# multivideo.net
KiCad netlist of a schematic drawn in EAGLE
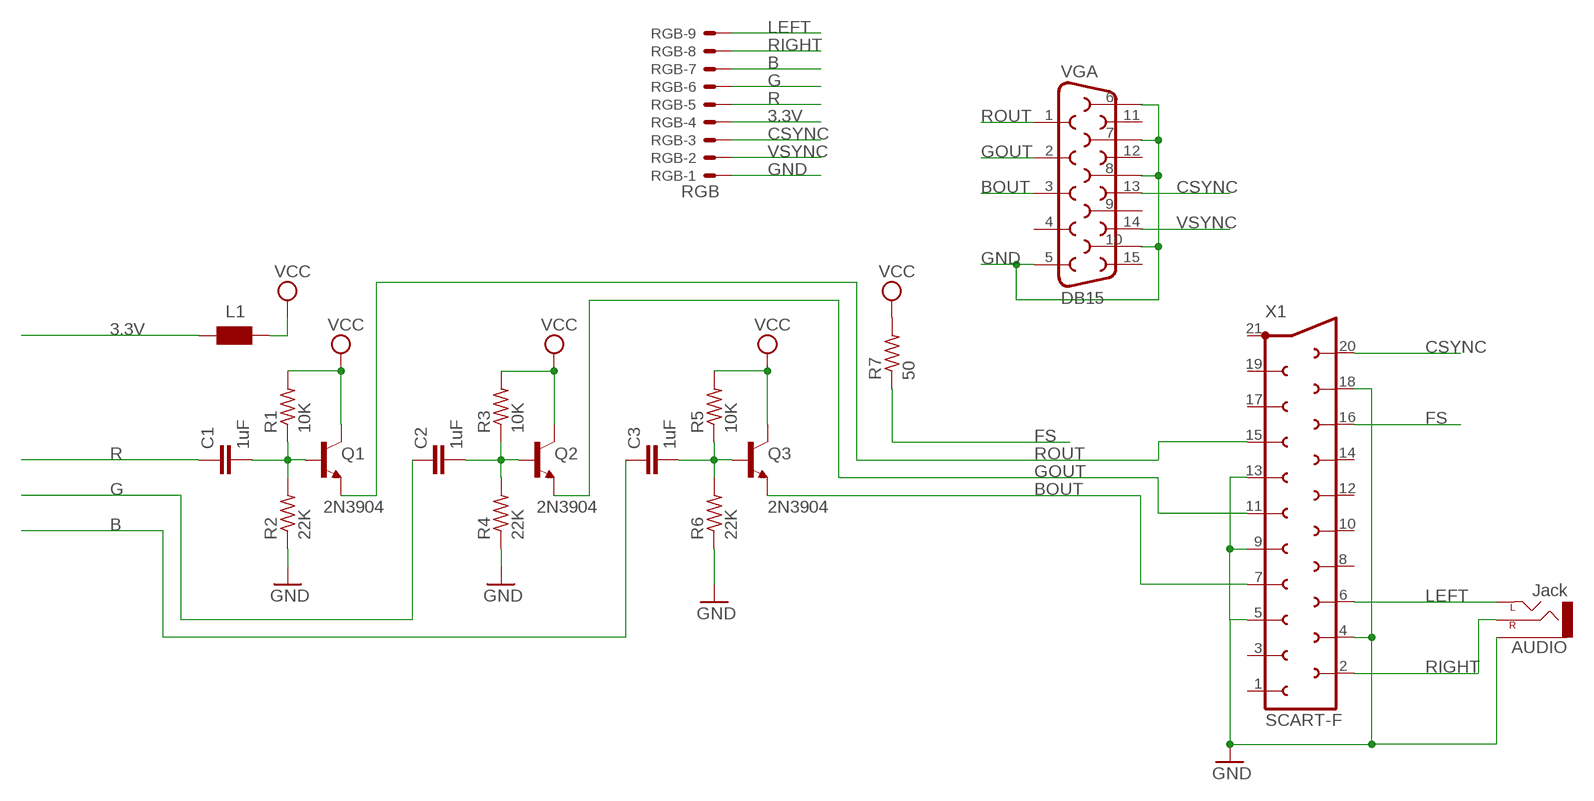
[diagram p0: schematic, sheet 1]

(export (version "E")
  (design (tool "Eeschema 10.0.6"))
  (components
    (comp (ref "AUDIO")
      (value "Jack")
      (footprint "eagle-import:AUDIO-JACK")
      (libsource (lib "eagle-import") (part "AUDIO-JACKPTH"))
    )
    (comp (ref "C1")
      (value "1uF")
      (footprint "eagle-import:C1206K")
      (libsource (lib "eagle-import") (part "C-EUC1206K"))
    )
    (comp (ref "C2")
      (value "1uF")
      (footprint "eagle-import:C1206K")
      (libsource (lib "eagle-import") (part "C-EUC1206K"))
    )
    (comp (ref "C3")
      (value "1uF")
      (footprint "eagle-import:C1206K")
      (libsource (lib "eagle-import") (part "C-EUC1206K"))
    )
    (comp (ref "L1")
      (value "WE-CBF_0805")
      (footprint "eagle-import:0805")
      (libsource (lib "eagle-import") (part "WE-CBF_0805"))
    )
    (comp (ref "Q1")
      (value "2N3904")
      (footprint "eagle-import:SOT23")
      (libsource (lib "eagle-import") (part "BC847SMDC"))
    )
    (comp (ref "Q2")
      (value "2N3904")
      (footprint "eagle-import:SOT23")
      (libsource (lib "eagle-import") (part "BC847SMDC"))
    )
    (comp (ref "Q3")
      (value "2N3904")
      (footprint "eagle-import:SOT23")
      (libsource (lib "eagle-import") (part "BC847SMDC"))
    )
    (comp (ref "R1")
      (value "10K")
      (footprint "eagle-import:R0805")
      (libsource (lib "eagle-import") (part "R-US_R0805"))
    )
    (comp (ref "R2")
      (value "22K")
      (footprint "eagle-import:R0805")
      (libsource (lib "eagle-import") (part "R-US_R0805"))
    )
    (comp (ref "R3")
      (value "10K")
      (footprint "eagle-import:R0805")
      (libsource (lib "eagle-import") (part "R-US_R0805"))
    )
    (comp (ref "R4")
      (value "22K")
      (footprint "eagle-import:R0805")
      (libsource (lib "eagle-import") (part "R-US_R0805"))
    )
    (comp (ref "R5")
      (value "10K")
      (footprint "eagle-import:R0805")
      (libsource (lib "eagle-import") (part "R-US_R0805"))
    )
    (comp (ref "R6")
      (value "22K")
      (footprint "eagle-import:R0805")
      (libsource (lib "eagle-import") (part "R-US_R0805"))
    )
    (comp (ref "R7")
      (value "50")
      (footprint "eagle-import:R0805")
      (libsource (lib "eagle-import") (part "R-US_R0805"))
    )
    (comp (ref "RGB")
      (value "RGB")
      (footprint "eagle-import:53048-09")
      (fields (field (name "MPN") "53048-0910"))
      (libsource (lib "eagle-import") (part "53?-09048"))
    )
    (comp (ref "VGA")
      (value "DB15")
      (footprint "eagle-import:DB15")
      (libsource (lib "eagle-import") (part "DB15"))
    )
    (comp (ref "X1")
      (value "SCART-F")
      (footprint "eagle-import:SCART-F")
      (libsource (lib "eagle-import") (part "SCART-F"))
    )
  )
  (nets
    (net (code "1") (name "/3.3V") (class "Default")
      (node (ref "L1") (pin "1") (pinfunction "1_1") (pintype "passive"))
      (node (ref "RGB") (pin "4") (pinfunction "S_4") (pintype "passive"))
    )
    (net (code "2") (name "/B") (class "Default")
      (node (ref "C3") (pin "1") (pinfunction "1_1") (pintype "passive"))
      (node (ref "RGB") (pin "7") (pinfunction "S_7") (pintype "passive"))
    )
    (net (code "3") (name "/BOUT") (class "Default")
      (node (ref "Q3") (pin "2") (pinfunction "E_2") (pintype "passive"))
      (node (ref "VGA") (pin "3") (pinfunction "3_3") (pintype "passive"))
      (node (ref "X1") (pin "7") (pinfunction "7_7") (pintype "passive"))
    )
    (net (code "4") (name "/CSYNC") (class "Default")
      (node (ref "RGB") (pin "3") (pinfunction "S_3") (pintype "passive"))
      (node (ref "VGA") (pin "13") (pinfunction "13_13") (pintype "passive"))
      (node (ref "X1") (pin "20") (pinfunction "20_20") (pintype "passive"))
    )
    (net (code "5") (name "/FS") (class "Default")
      (node (ref "R7") (pin "1") (pinfunction "1_1") (pintype "passive"))
      (node (ref "X1") (pin "16") (pinfunction "16_16") (pintype "passive"))
    )
    (net (code "6") (name "/G") (class "Default")
      (node (ref "C2") (pin "1") (pinfunction "1_1") (pintype "passive"))
      (node (ref "RGB") (pin "6") (pinfunction "S_6") (pintype "passive"))
    )
    (net (code "7") (name "/GOUT") (class "Default")
      (node (ref "Q2") (pin "2") (pinfunction "E_2") (pintype "passive"))
      (node (ref "VGA") (pin "2") (pinfunction "2_2") (pintype "passive"))
      (node (ref "X1") (pin "11") (pinfunction "11_11") (pintype "passive"))
    )
    (net (code "8") (name "/LEFT") (class "Default")
      (node (ref "AUDIO") (pin "TIP") (pinfunction "LEFT_TIP") (pintype "bidirectional"))
      (node (ref "RGB") (pin "9") (pinfunction "S_9") (pintype "passive"))
      (node (ref "X1") (pin "6") (pinfunction "6_6") (pintype "passive"))
    )
    (net (code "9") (name "/R") (class "Default")
      (node (ref "C1") (pin "1") (pinfunction "1_1") (pintype "passive"))
      (node (ref "RGB") (pin "5") (pinfunction "S_5") (pintype "passive"))
    )
    (net (code "10") (name "/RIGHT") (class "Default")
      (node (ref "AUDIO") (pin "RING") (pinfunction "RIGHT_RING") (pintype "bidirectional"))
      (node (ref "RGB") (pin "8") (pinfunction "S_8") (pintype "passive"))
      (node (ref "X1") (pin "2") (pinfunction "2_2") (pintype "passive"))
    )
    (net (code "11") (name "/ROUT") (class "Default")
      (node (ref "Q1") (pin "2") (pinfunction "E_2") (pintype "passive"))
      (node (ref "VGA") (pin "1") (pinfunction "1_1") (pintype "passive"))
      (node (ref "X1") (pin "15") (pinfunction "15_15") (pintype "passive"))
    )
    (net (code "12") (name "/VSYNC") (class "Default")
      (node (ref "RGB") (pin "2") (pinfunction "S_2") (pintype "passive"))
      (node (ref "VGA") (pin "14") (pinfunction "14_14") (pintype "passive"))
    )
    (net (code "13") (name "GND") (class "Default")
      (node (ref "AUDIO") (pin "SLEEVE") (pinfunction "SLEEVE_SLEEVE") (pintype "bidirectional"))
      (node (ref "R2") (pin "1") (pinfunction "1_1") (pintype "passive"))
      (node (ref "R4") (pin "1") (pinfunction "1_1") (pintype "passive"))
      (node (ref "R6") (pin "1") (pinfunction "1_1") (pintype "passive"))
      (node (ref "RGB") (pin "1") (pinfunction "S_1") (pintype "passive"))
      (node (ref "VGA") (pin "10") (pinfunction "10_10") (pintype "passive"))
      (node (ref "VGA") (pin "5") (pinfunction "5_5") (pintype "passive"))
      (node (ref "VGA") (pin "6") (pinfunction "6_6") (pintype "passive"))
      (node (ref "VGA") (pin "7") (pinfunction "7_7") (pintype "passive"))
      (node (ref "VGA") (pin "8") (pinfunction "8_8") (pintype "passive"))
      (node (ref "X1") (pin "13") (pinfunction "13_13") (pintype "passive"))
      (node (ref "X1") (pin "18") (pinfunction "18_18") (pintype "passive"))
      (node (ref "X1") (pin "4") (pinfunction "4_4") (pintype "passive"))
      (node (ref "X1") (pin "5") (pinfunction "5_5") (pintype "passive"))
      (node (ref "X1") (pin "9") (pinfunction "9_9") (pintype "passive"))
    )
    (net (code "14") (name "Net-(Q1-B)") (class "Default")
      (node (ref "C1") (pin "2") (pinfunction "2_2") (pintype "passive"))
      (node (ref "Q1") (pin "1") (pinfunction "B_1") (pintype "passive"))
      (node (ref "R1") (pin "1") (pinfunction "1_1") (pintype "passive"))
      (node (ref "R2") (pin "2") (pinfunction "2_2") (pintype "passive"))
    )
    (net (code "15") (name "Net-(Q2-B)") (class "Default")
      (node (ref "C2") (pin "2") (pinfunction "2_2") (pintype "passive"))
      (node (ref "Q2") (pin "1") (pinfunction "B_1") (pintype "passive"))
      (node (ref "R3") (pin "1") (pinfunction "1_1") (pintype "passive"))
      (node (ref "R4") (pin "2") (pinfunction "2_2") (pintype "passive"))
    )
    (net (code "16") (name "Net-(Q3-B)") (class "Default")
      (node (ref "C3") (pin "2") (pinfunction "2_2") (pintype "passive"))
      (node (ref "Q3") (pin "1") (pinfunction "B_1") (pintype "passive"))
      (node (ref "R5") (pin "1") (pinfunction "1_1") (pintype "passive"))
      (node (ref "R6") (pin "2") (pinfunction "2_2") (pintype "passive"))
    )
    (net (code "17") (name "VCC") (class "Default")
      (node (ref "L1") (pin "2") (pinfunction "2_2") (pintype "passive"))
      (node (ref "Q1") (pin "3") (pinfunction "C_3") (pintype "passive"))
      (node (ref "Q2") (pin "3") (pinfunction "C_3") (pintype "passive"))
      (node (ref "Q3") (pin "3") (pinfunction "C_3") (pintype "passive"))
      (node (ref "R1") (pin "2") (pinfunction "2_2") (pintype "passive"))
      (node (ref "R3") (pin "2") (pinfunction "2_2") (pintype "passive"))
      (node (ref "R5") (pin "2") (pinfunction "2_2") (pintype "passive"))
      (node (ref "R7") (pin "2") (pinfunction "2_2") (pintype "passive"))
    )
    (net (code "18") (name "unconnected-(VGA-Pad4)") (class "Default")
      (node (ref "VGA") (pin "4") (pinfunction "4_4") (pintype "passive"))
    )
    (net (code "19") (name "unconnected-(VGA-Pad9)") (class "Default")
      (node (ref "VGA") (pin "9") (pinfunction "9_9") (pintype "passive"))
    )
    (net (code "20") (name "unconnected-(VGA-Pad11)") (class "Default")
      (node (ref "VGA") (pin "11") (pinfunction "11_11") (pintype "passive"))
    )
    (net (code "21") (name "unconnected-(VGA-Pad12)") (class "Default")
      (node (ref "VGA") (pin "12") (pinfunction "12_12") (pintype "passive"))
    )
    (net (code "22") (name "unconnected-(VGA-Pad15)") (class "Default")
      (node (ref "VGA") (pin "15") (pinfunction "15_15") (pintype "passive"))
    )
    (net (code "23") (name "unconnected-(X1-Pad1)") (class "Default")
      (node (ref "X1") (pin "1") (pinfunction "1_1") (pintype "passive"))
    )
    (net (code "24") (name "unconnected-(X1-Pad3)") (class "Default")
      (node (ref "X1") (pin "3") (pinfunction "3_3") (pintype "passive"))
    )
    (net (code "25") (name "unconnected-(X1-Pad8)") (class "Default")
      (node (ref "X1") (pin "8") (pinfunction "8_8") (pintype "passive"))
    )
    (net (code "26") (name "unconnected-(X1-Pad10)") (class "Default")
      (node (ref "X1") (pin "10") (pinfunction "10_10") (pintype "passive"))
    )
    (net (code "27") (name "unconnected-(X1-Pad12)") (class "Default")
      (node (ref "X1") (pin "12") (pinfunction "12_12") (pintype "passive"))
    )
    (net (code "28") (name "unconnected-(X1-Pad14)") (class "Default")
      (node (ref "X1") (pin "14") (pinfunction "14_14") (pintype "passive"))
    )
    (net (code "29") (name "unconnected-(X1-Pad17)") (class "Default")
      (node (ref "X1") (pin "17") (pinfunction "17_17") (pintype "passive"))
    )
    (net (code "30") (name "unconnected-(X1-Pad19)") (class "Default")
      (node (ref "X1") (pin "19") (pinfunction "19_19") (pintype "passive"))
    )
    (net (code "31") (name "unconnected-(X1-Pad21)") (class "Default")
      (node (ref "X1") (pin "21") (pinfunction "21_21") (pintype "passive"))
    )
  )
)
